# Morpheus_LED1.net
KiCad netlist of a schematic drawn in Altium Designer
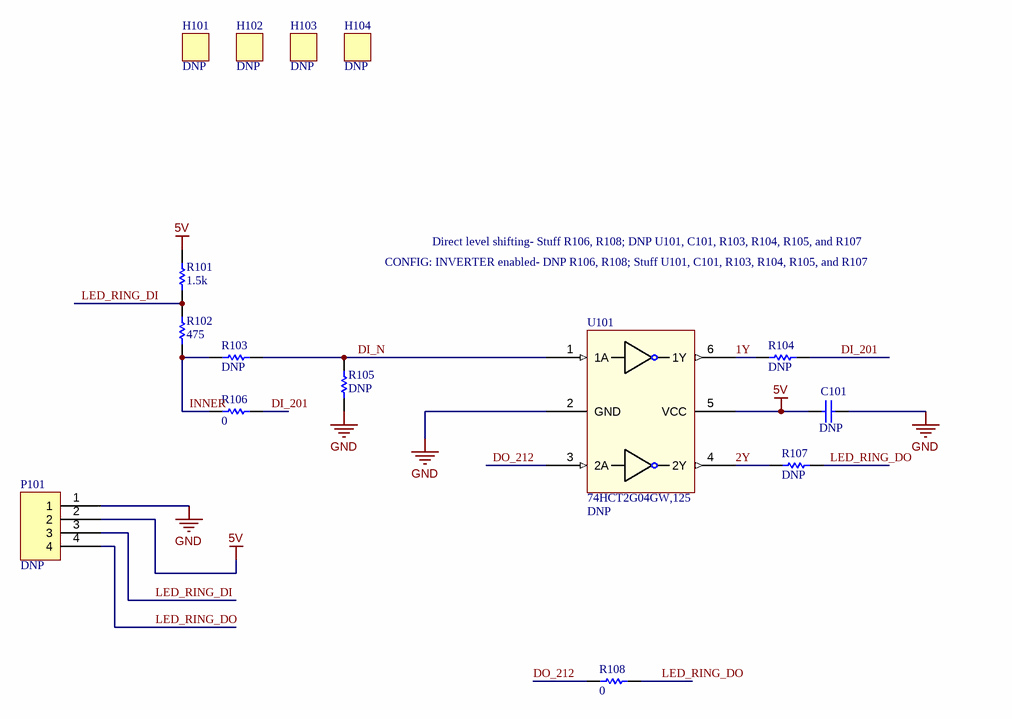
[diagram p0: Morpheus_LED1.SchDoc]

(export (version "E")
  (design (tool "Eeschema 10.0.6"))
  (components
    (comp (ref "C101")
      (value "DNP")
      (footprint "CAP0402_SENSE_DVT")
      (description "Chip capacitor")
      (fields (field (name "TOLERANCE") "10%") (field (name "VOLTAGE") "50V"))
      (libsource (lib "Hello") (part "C_0.1u_10_50_X7R_0402"))
    )
    (comp (ref "H101")
      (value "DNP")
      (footprint "HOLE_ROUND_1.4mm")
      (description "general purpose hole")
      (libsource (lib "Hello") (part "Hole"))
    )
    (comp (ref "H102")
      (value "DNP")
      (footprint "HOLE_ROUND_1.4mm")
      (description "general purpose hole")
      (libsource (lib "Hello") (part "Hole"))
    )
    (comp (ref "H103")
      (value "DNP")
      (footprint "HOLE_ROUND_1.4mm")
      (description "general purpose hole")
      (libsource (lib "Hello") (part "Hole"))
    )
    (comp (ref "H104")
      (value "DNP")
      (footprint "HOLE_ROUND_1.4mm")
      (description "general purpose hole")
      (libsource (lib "Hello") (part "Hole"))
    )
    (comp (ref "P101")
      (value "DNP")
      (footprint "mate_for_molex_47420-0001")
      (description "Molex 4-pin spring connector 1.8 mm working height")
      (libsource (lib "Hello") (part "mate_for_molex_47420-0001"))
    )
    (comp (ref "R101")
      (value "1.5k")
      (footprint "RES0402_SENSE_DVT")
      (description "Chip Resistor")
      (fields (field (name "TOLERANCE") "5 %") (field (name "POWER") "0.1 W"))
      (libsource (lib "Hello") (part "R_1.5k_5_0.1_0402"))
    )
    (comp (ref "R102")
      (value "475")
      (footprint "RES0402_SENSE_DVT")
      (description "Chip Resistor")
      (fields (field (name "TOLERANCE") "1 %") (field (name "POWER") "0.1 W"))
      (libsource (lib "Hello") (part "R_475_1_0.1_0402"))
    )
    (comp (ref "R103")
      (value "DNP")
      (footprint "RES0402_SENSE_DVT")
      (description "Chip Resistor")
      (fields (field (name "TOLERANCE") "Jumper") (field (name "POWER") "0.1 W"))
      (libsource (lib "Hello") (part "R_0_jumper_0.1_0402"))
    )
    (comp (ref "R104")
      (value "DNP")
      (footprint "RES0402_SENSE_DVT")
      (description "Chip Resistor")
      (fields (field (name "TOLERANCE") "1 %") (field (name "POWER") "0.1 W"))
      (libsource (lib "Hello") (part "R_100_1_0.1_0402"))
    )
    (comp (ref "R105")
      (value "DNP")
      (footprint "RES0402_SENSE_DVT")
      (description "Chip Resistor")
      (fields (field (name "TOLERANCE") "5 %") (field (name "POWER") "0.1 W"))
      (libsource (lib "Hello") (part "R_1.5k_5_0.1_0402"))
    )
    (comp (ref "R106")
      (value "0")
      (footprint "RES0402_SENSE_DVT")
      (description "Chip Resistor")
      (fields (field (name "TOLERANCE") "Jumper") (field (name "POWER") "0.1 W"))
      (libsource (lib "Hello") (part "R_0_jumper_0.1_0402"))
    )
    (comp (ref "R107")
      (value "DNP")
      (footprint "RES0402_SENSE_DVT")
      (description "Chip Resistor")
      (fields (field (name "TOLERANCE") "1 %") (field (name "POWER") "0.1 W"))
      (libsource (lib "Hello") (part "R_100_1_0.1_0402"))
    )
    (comp (ref "R108")
      (value "0")
      (footprint "RES0402_SENSE_DVT")
      (description "Chip Resistor")
      (fields (field (name "TOLERANCE") "Jumper") (field (name "POWER") "0.1 W"))
      (libsource (lib "Hello") (part "R_0_jumper_0.1_0402"))
    )
    (comp (ref "U101")
      (value "DNP")
      (footprint "SOT65P210X110-6N")
      (description "Dual inverter The 74HC2G04; 74HCT2G04 is a high-speed Si-gate CMOS device.")
      (fields (field (name "PN") "74HCT2G04GW,125"))
      (libsource (lib "Hello") (part "74HCT2G04"))
    )
  )
  (nets
    (net (code "1") (name "/1Y") (class "Default")
      (node (ref "R104") (pin "1") (pinfunction "1_1") (pintype "passive"))
      (node (ref "U101") (pin "6") (pinfunction "1Y_6") (pintype "output"))
    )
    (net (code "2") (name "/2Y") (class "Default")
      (node (ref "R107") (pin "1") (pinfunction "1_1") (pintype "passive"))
      (node (ref "U101") (pin "4") (pinfunction "2Y_4") (pintype "output"))
    )
    (net (code "3") (name "/DI_201") (class "Default")
      (node (ref "R104") (pin "2") (pinfunction "2_2") (pintype "passive"))
      (node (ref "R106") (pin "2") (pinfunction "2_2") (pintype "passive"))
    )
    (net (code "4") (name "/DI_N") (class "Default")
      (node (ref "R103") (pin "2") (pinfunction "2_2") (pintype "passive"))
      (node (ref "R105") (pin "2") (pinfunction "2_2") (pintype "passive"))
      (node (ref "U101") (pin "1") (pinfunction "1A_1") (pintype "input"))
    )
    (net (code "5") (name "/DO_212") (class "Default")
      (node (ref "R108") (pin "1") (pinfunction "1_1") (pintype "passive"))
      (node (ref "U101") (pin "3") (pinfunction "2A_3") (pintype "input"))
    )
    (net (code "6") (name "/INNER") (class "Default")
      (node (ref "R102") (pin "1") (pinfunction "1_1") (pintype "passive"))
      (node (ref "R103") (pin "1") (pinfunction "1_1") (pintype "passive"))
      (node (ref "R106") (pin "1") (pinfunction "1_1") (pintype "passive"))
    )
    (net (code "7") (name "/LED_RING_DI") (class "Default")
      (node (ref "P101") (pin "3") (pinfunction "3_3") (pintype "passive"))
      (node (ref "R101") (pin "1") (pinfunction "1_1") (pintype "passive"))
      (node (ref "R102") (pin "2") (pinfunction "2_2") (pintype "passive"))
    )
    (net (code "8") (name "/LED_RING_DO") (class "Default")
      (node (ref "P101") (pin "4") (pinfunction "4_4") (pintype "passive"))
      (node (ref "R107") (pin "2") (pinfunction "2_2") (pintype "passive"))
      (node (ref "R108") (pin "2") (pinfunction "2_2") (pintype "passive"))
    )
    (net (code "9") (name "5V") (class "Default")
      (node (ref "C101") (pin "1") (pinfunction "1_1") (pintype "passive"))
      (node (ref "P101") (pin "2") (pinfunction "2_2") (pintype "passive"))
      (node (ref "R101") (pin "2") (pinfunction "2_2") (pintype "passive"))
      (node (ref "U101") (pin "5") (pinfunction "VCC_5") (pintype "power_in"))
    )
    (net (code "10") (name "GND") (class "Default")
      (node (ref "C101") (pin "2") (pinfunction "2_2") (pintype "passive"))
      (node (ref "P101") (pin "1") (pinfunction "1_1") (pintype "passive"))
      (node (ref "R105") (pin "1") (pinfunction "1_1") (pintype "passive"))
      (node (ref "U101") (pin "2") (pinfunction "GND_2") (pintype "power_in"))
    )
  )
)
